# Sheet1.net
KiCad netlist of a schematic drawn in Altium Designer
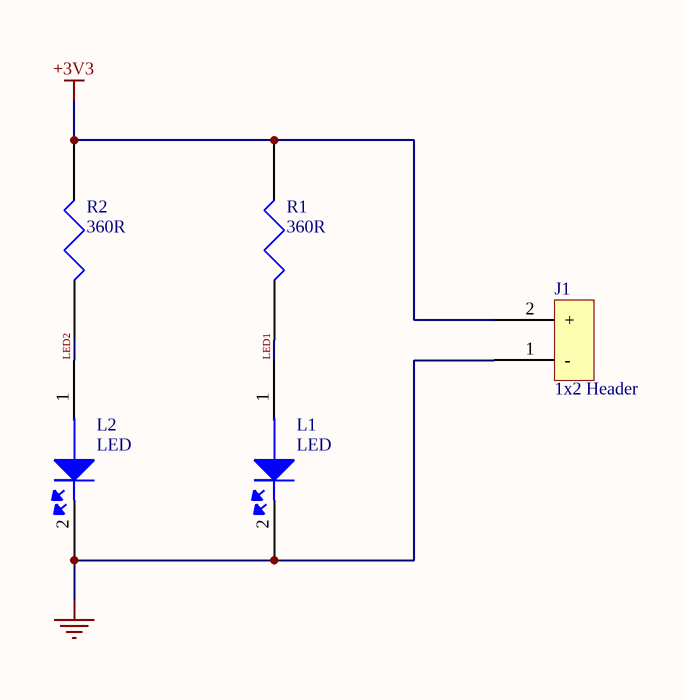
[diagram p0: Sheet1.SchDoc]

(export (version "E")
  (design (tool "Eeschema 10.0.6"))
  (components
    (comp (ref "J1")
      (value "1x2 Header")
      (footprint "header1x2")
      (description "Connector Wire to Board Header 2 Position 2.54mm Solder Stra")
      (fields (field (name "MANUFACTURER") "Molex") (field (name "MANUFACTURER PART NUMBER") "22-23-2021"))
      (libsource (lib "Schlib1") (part "22-23-2021"))
    )
    (comp (ref "L1")
      (value "LED")
      (footprint "LED")
      (description "CHIPLED, 0603, BLUE, 11.5MCD, 470NM")
      (fields
        (field (name "MANUFACTURER") "Panasonic SSG")
        (field (name "MANUFACTURER PART NUMBER") "LNJ926W8CRA")
      )
      (libsource (lib "Schlib1") (part "LNJ926W8CRA"))
    )
    (comp (ref "L2")
      (value "LED")
      (footprint "LED")
      (description "CHIPLED, 0603, BLUE, 11.5MCD, 470NM")
      (fields
        (field (name "MANUFACTURER") "Panasonic SSG")
        (field (name "MANUFACTURER PART NUMBER") "LNJ926W8CRA")
      )
      (libsource (lib "Schlib1") (part "LNJ926W8CRA"))
    )
    (comp (ref "R1")
      (value "360R")
      (footprint "R0805")
      (description "Res Thick Film 0805 360 Ohm 1% 0.125W(1/8W) ±100ppm/C Molded SMD Automotive Paper T/R")
      (fields
        (field (name "MANUFACTURER") "Vishay")
        (field (name "MANUFACTURER PART NUMBER") "CRCW0805360RFKEA")
      )
      (libsource (lib "Schlib1") (part "CRCW0805360RFKEA"))
    )
    (comp (ref "R2")
      (value "360R")
      (footprint "R0805")
      (description "Res Thick Film 0805 360 Ohm 1% 0.125W(1/8W) ±100ppm/C Molded SMD Automotive Paper T/R")
      (fields
        (field (name "MANUFACTURER") "Vishay")
        (field (name "MANUFACTURER PART NUMBER") "CRCW0805360RFKEA")
      )
      (libsource (lib "Schlib1") (part "CRCW0805360RFKEA"))
    )
  )
  (nets
    (net (code "1") (name "+3V3") (class "Default")
      (node (ref "J1") (pin "2") (pinfunction "+_2") (pintype "passive"))
      (node (ref "R1") (pin "2") (pinfunction "2_2") (pintype "passive"))
      (node (ref "R2") (pin "2") (pinfunction "2_2") (pintype "passive"))
    )
    (net (code "2") (name "/LED1") (class "Default")
      (node (ref "L1") (pin "1") (pinfunction "1_1") (pintype "passive"))
      (node (ref "R1") (pin "1") (pinfunction "1_1") (pintype "passive"))
    )
    (net (code "3") (name "/LED2") (class "Default")
      (node (ref "L2") (pin "1") (pinfunction "1_1") (pintype "passive"))
      (node (ref "R2") (pin "1") (pinfunction "1_1") (pintype "passive"))
    )
    (net (code "4") (name "GND") (class "Default")
      (node (ref "J1") (pin "1") (pinfunction "-_1") (pintype "passive"))
      (node (ref "L1") (pin "2") (pinfunction "2_2") (pintype "passive"))
      (node (ref "L2") (pin "2") (pinfunction "2_2") (pintype "passive"))
    )
  )
)
